# Sheet1.net
KiCad netlist of a schematic drawn in Altium Designer
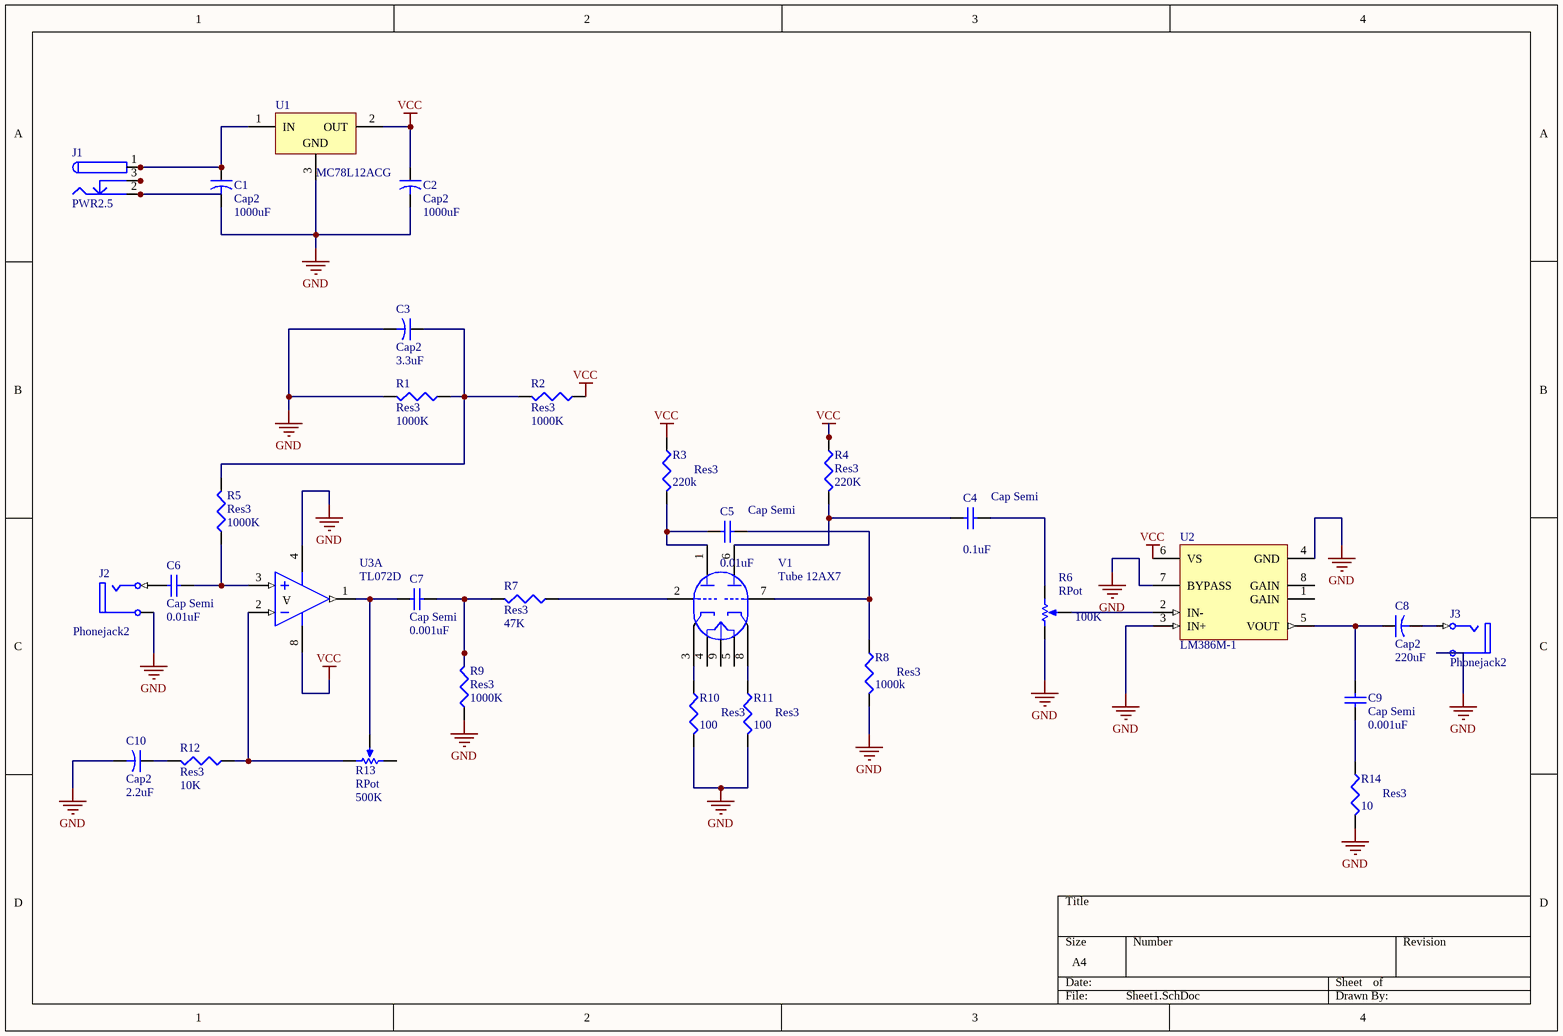
[diagram p0: Sheet1.SchDoc]

(export (version "E")
  (design (tool "Eeschema 10.0.6"))
  (components
    (comp (ref "C1")
      (value "Cap2")
      (footprint "CAPR5-4X5")
      (description "Capacitor")
      (fields (field (name "ALTIUM_VALUE") "1000uF") (field (name "PUBLISHER") "Altium Limited"))
      (libsource (lib "Miscellaneous Devices") (part "Cap2"))
    )
    (comp (ref "C2")
      (value "Cap2")
      (footprint "CAPR5-4X5")
      (description "Capacitor")
      (fields (field (name "ALTIUM_VALUE") "1000uF") (field (name "PUBLISHER") "Altium Limited"))
      (libsource (lib "Miscellaneous Devices") (part "Cap2"))
    )
    (comp (ref "C3")
      (value "Cap2")
      (footprint "CAPR5-4X5")
      (description "Capacitor")
      (fields (field (name "ALTIUM_VALUE") "3.3uF") (field (name "PUBLISHER") "Altium Limited"))
      (libsource (lib "Miscellaneous Devices") (part "Cap2"))
    )
    (comp (ref "C4")
      (value "Cap Semi")
      (footprint "C1206")
      (description "Capacitor (Semiconductor SIM Model)")
      (fields (field (name "ALTIUM_VALUE") "0.1uF") (field (name "PUBLISHER") "Altium Limited"))
      (libsource (lib "Miscellaneous Devices") (part "Cap Semi"))
    )
    (comp (ref "C5")
      (value "Cap Semi")
      (footprint "C1206")
      (description "Capacitor (Semiconductor SIM Model)")
      (fields (field (name "ALTIUM_VALUE") "0.01uF") (field (name "PUBLISHER") "Altium Limited"))
      (libsource (lib "Miscellaneous Devices") (part "Cap Semi"))
    )
    (comp (ref "C6")
      (value "Cap Semi")
      (footprint "1608[0603]")
      (description "Capacitor (Semiconductor SIM Model)")
      (fields (field (name "ALTIUM_VALUE") "0.01uF") (field (name "PUBLISHER") "Altium Limited"))
      (libsource (lib "Miscellaneous Devices") (part "Cap Semi"))
    )
    (comp (ref "C7")
      (value "Cap Semi")
      (footprint "C1206")
      (description "Capacitor (Semiconductor SIM Model)")
      (fields (field (name "ALTIUM_VALUE") "0.001uF") (field (name "PUBLISHER") "Altium Limited"))
      (libsource (lib "Miscellaneous Devices") (part "Cap Semi"))
    )
    (comp (ref "C8")
      (value "Cap2")
      (footprint "CAPR5-4X5")
      (description "Capacitor")
      (fields (field (name "ALTIUM_VALUE") "220uF") (field (name "PUBLISHER") "Altium Limited"))
      (libsource (lib "Miscellaneous Devices") (part "Cap2"))
    )
    (comp (ref "C9")
      (value "Cap Semi")
      (footprint "C1206")
      (description "Capacitor (Semiconductor SIM Model)")
      (fields (field (name "ALTIUM_VALUE") "0.001uF") (field (name "PUBLISHER") "Altium Limited"))
      (libsource (lib "Miscellaneous Devices") (part "Cap Semi"))
    )
    (comp (ref "C10")
      (value "Cap2")
      (footprint "CAPR5-4X5")
      (description "Capacitor")
      (fields (field (name "ALTIUM_VALUE") "2.2uF") (field (name "PUBLISHER") "Altium Limited"))
      (libsource (lib "Miscellaneous Devices") (part "Cap2"))
    )
    (comp (ref "J1")
      (value "PWR2.5")
      (footprint "KLD-0202")
      (description "Low Voltage Power Supply Connector")
      (fields (field (name "PUBLISHER") "Altium Limited"))
      (libsource (lib "Miscellaneous Connectors") (part "PWR2.5"))
    )
    (comp (ref "J2")
      (value "Phonejack2")
      (footprint "JACK/6-V2")
      (description "Jack Socket, 1/4\" [6.5mm], Thru-Hole, Vertical, 2-Conductor Open Circuit")
      (fields (field (name "PUBLISHER") "Altium Limited"))
      (libsource (lib "Miscellaneous Connectors") (part "Phonejack2"))
    )
    (comp (ref "J3")
      (value "Phonejack2")
      (footprint "JACK/6-V2")
      (description "Jack Socket, 1/4\" [6.5mm], Thru-Hole, Vertical, 2-Conductor Open Circuit")
      (fields (field (name "PUBLISHER") "Altium Limited"))
      (libsource (lib "Miscellaneous Connectors") (part "Phonejack2"))
    )
    (comp (ref "R1")
      (value "Res3")
      (footprint "J1-0603")
      (description "Resistor")
      (fields (field (name "ALTIUM_VALUE") "1000K") (field (name "PUBLISHER") "Altium Limited"))
      (libsource (lib "Miscellaneous Devices") (part "Res3"))
    )
    (comp (ref "R2")
      (value "Res3")
      (footprint "J1-0603")
      (description "Resistor")
      (fields (field (name "ALTIUM_VALUE") "1000K") (field (name "PUBLISHER") "Altium Limited"))
      (libsource (lib "Miscellaneous Devices") (part "Res3"))
    )
    (comp (ref "R3")
      (value "Res3")
      (footprint "J1-0603")
      (description "Resistor")
      (fields (field (name "ALTIUM_VALUE") "220k") (field (name "PUBLISHER") "Altium Limited"))
      (libsource (lib "Miscellaneous Devices") (part "Res3"))
    )
    (comp (ref "R4")
      (value "Res3")
      (footprint "J1-0603")
      (description "Resistor")
      (fields (field (name "ALTIUM_VALUE") "220K") (field (name "PUBLISHER") "Altium Limited"))
      (libsource (lib "Miscellaneous Devices") (part "Res3"))
    )
    (comp (ref "R5")
      (value "Res3")
      (footprint "J1-0603")
      (description "Resistor")
      (fields (field (name "ALTIUM_VALUE") "1000K") (field (name "PUBLISHER") "Altium Limited"))
      (libsource (lib "Miscellaneous Devices") (part "Res3"))
    )
    (comp (ref "R6")
      (value "RPot")
      (footprint "VR5")
      (description "Potentiometer")
      (fields (field (name "ALTIUM_VALUE") "100K") (field (name "PUBLISHER") "Altium Limited"))
      (libsource (lib "Miscellaneous Devices") (part "RPot"))
    )
    (comp (ref "R7")
      (value "Res3")
      (footprint "J1-0603")
      (description "Resistor")
      (fields (field (name "ALTIUM_VALUE") "47K") (field (name "PUBLISHER") "Altium Limited"))
      (libsource (lib "Miscellaneous Devices") (part "Res3"))
    )
    (comp (ref "R8")
      (value "Res3")
      (footprint "J1-0603")
      (description "Resistor")
      (fields (field (name "ALTIUM_VALUE") "1000k") (field (name "PUBLISHER") "Altium Limited"))
      (libsource (lib "Miscellaneous Devices") (part "Res3"))
    )
    (comp (ref "R9")
      (value "Res3")
      (footprint "J1-0603")
      (description "Resistor")
      (fields (field (name "ALTIUM_VALUE") "1000K") (field (name "PUBLISHER") "Altium Limited"))
      (libsource (lib "Miscellaneous Devices") (part "Res3"))
    )
    (comp (ref "R10")
      (value "Res3")
      (footprint "J1-0603")
      (description "Resistor")
      (fields (field (name "ALTIUM_VALUE") "100") (field (name "PUBLISHER") "Altium Limited"))
      (libsource (lib "Miscellaneous Devices") (part "Res3"))
    )
    (comp (ref "R11")
      (value "Res3")
      (footprint "J1-0603")
      (description "Resistor")
      (fields (field (name "ALTIUM_VALUE") "100") (field (name "PUBLISHER") "Altium Limited"))
      (libsource (lib "Miscellaneous Devices") (part "Res3"))
    )
    (comp (ref "R12")
      (value "Res3")
      (footprint "J1-0603")
      (description "Resistor")
      (fields (field (name "ALTIUM_VALUE") "10K") (field (name "PUBLISHER") "Altium Limited"))
      (libsource (lib "Miscellaneous Devices") (part "Res3"))
    )
    (comp (ref "R13")
      (value "RPot")
      (footprint "VR5")
      (description "Potentiometer")
      (fields (field (name "ALTIUM_VALUE") "500K") (field (name "PUBLISHER") "Altium Limited"))
      (libsource (lib "Miscellaneous Devices") (part "RPot"))
    )
    (comp (ref "R14")
      (value "Res3")
      (footprint "J1-0603")
      (description "Resistor")
      (fields (field (name "ALTIUM_VALUE") "10") (field (name "PUBLISHER") "Altium Limited"))
      (libsource (lib "Miscellaneous Devices") (part "Res3"))
    )
    (comp (ref "U1")
      (value "MC78L12ACG")
      (footprint "79-05")
      (description "3-Terminal Low-Current Positive Fixed Voltage Regulator")
      (fields (field (name "PUBLISHER") "Altium Limited"))
      (libsource (lib "Motorola Power Mgt Voltage Regulator") (part "MC78L12ACG"))
    )
    (comp (ref "U2")
      (value "LM386M-1")
      (footprint "M08A_N")
      (description "Low Voltage Audio Power Amplifier, 8-pin Narrow SOIC")
      (fields
        (field (name "MANUFACTURER") "National Semiconductor")
        (field (name "PUBLISHER") "Altium Limited")
      )
      (libsource (lib "NSC Audio") (part "LM386M-1"))
    )
    (comp (ref "U3")
      (value "TL072D")
      (footprint "D008_M")
      (description "Low-Noise JFET-Input Operational Amplifier")
      (fields (field (name "PUBLISHER") "Altium Limited"))
      (libsource (lib "TI Operational Amplifier") (part "TL072D"))
    )
    (comp (ref "V1")
      (value "Tube 12AX7")
      (footprint "VTUBE-9")
      (description "High Mu Dual Triode")
      (fields (field (name "PUBLISHER") "Altium Limited"))
      (libsource (lib "Miscellaneous Devices") (part "Tube 12AX7"))
    )
  )
  (nets
    (net (code "1") (name "GND") (class "Default")
      (node (ref "C1") (pin "2") (pinfunction "2_2") (pintype "passive"))
      (node (ref "C10") (pin "2") (pinfunction "2_2") (pintype "passive"))
      (node (ref "C2") (pin "2") (pinfunction "2_2") (pintype "passive"))
      (node (ref "C3") (pin "2") (pinfunction "2_2") (pintype "passive"))
      (node (ref "J2") (pin "5") (pinfunction "S_5") (pintype "power_in"))
      (node (ref "J3") (pin "5") (pinfunction "S_5") (pintype "power_in"))
      (node (ref "R1") (pin "2") (pinfunction "2_2") (pintype "passive"))
      (node (ref "R10") (pin "2") (pinfunction "2_2") (pintype "passive"))
      (node (ref "R11") (pin "2") (pinfunction "2_2") (pintype "passive"))
      (node (ref "R14") (pin "2") (pinfunction "2_2") (pintype "passive"))
      (node (ref "R6") (pin "1") (pinfunction "TOP_1") (pintype "passive"))
      (node (ref "R8") (pin "2") (pinfunction "2_2") (pintype "passive"))
      (node (ref "R9") (pin "1") (pinfunction "1_1") (pintype "passive"))
      (node (ref "U1") (pin "3") (pinfunction "GND_3") (pintype "power_in"))
      (node (ref "U2") (pin "3") (pinfunction "IN+_3") (pintype "input"))
      (node (ref "U2") (pin "4") (pinfunction "GND_4") (pintype "power_in"))
      (node (ref "U2") (pin "7") (pinfunction "BYPASS_7") (pintype "passive"))
      (node (ref "U3") (pin "4") (pinfunction "V-_4") (pintype "power_in"))
    )
    (net (code "2") (name "Net-(C3-Pad1)") (class "Default")
      (node (ref "C3") (pin "1") (pinfunction "1_1") (pintype "passive"))
      (node (ref "R1") (pin "1") (pinfunction "1_1") (pintype "passive"))
      (node (ref "R2") (pin "2") (pinfunction "2_2") (pintype "passive"))
      (node (ref "R5") (pin "2") (pinfunction "2_2") (pintype "passive"))
    )
    (net (code "3") (name "Net-(C7-Pad2)") (class "Default")
      (node (ref "C7") (pin "2") (pinfunction "2_2") (pintype "passive"))
      (node (ref "R7") (pin "2") (pinfunction "2_2") (pintype "passive"))
      (node (ref "R9") (pin "2") (pinfunction "2_2") (pintype "passive"))
    )
    (net (code "4") (name "Net-(C9-Pad1)") (class "Default")
      (node (ref "C9") (pin "1") (pinfunction "1_1") (pintype "passive"))
      (node (ref "R14") (pin "1") (pinfunction "1_1") (pintype "passive"))
    )
    (net (code "5") (name "Net-(C10-Pad1)") (class "Default")
      (node (ref "C10") (pin "1") (pinfunction "1_1") (pintype "passive"))
      (node (ref "R12") (pin "2") (pinfunction "2_2") (pintype "passive"))
    )
    (net (code "6") (name "Net-(J1-Pad2)") (class "Default")
      (node (ref "J1") (pin "2") (pinfunction "2_2") (pintype "power_in"))
      (node (ref "J1") (pin "2A") (pinfunction "2A_2A") (pintype "power_in"))
      (node (ref "J1") (pin "2B") (pinfunction "2B_2B") (pintype "power_in"))
    )
    (net (code "7") (name "Net-(J1-Pad3)") (class "Default")
      (node (ref "J1") (pin "3") (pinfunction "3_3") (pintype "power_in"))
      (node (ref "J1") (pin "3A") (pinfunction "3A_3A") (pintype "power_in"))
      (node (ref "J1") (pin "3B") (pinfunction "3B_3B") (pintype "power_in"))
    )
    (net (code "8") (name "Net-(J2-T)") (class "Default")
      (node (ref "C6") (pin "1") (pinfunction "1_1") (pintype "passive"))
      (node (ref "J2") (pin "1") (pinfunction "T_1") (pintype "input"))
    )
    (net (code "9") (name "Net-(J3-T)") (class "Default")
      (node (ref "C8") (pin "2") (pinfunction "2_2") (pintype "passive"))
      (node (ref "J3") (pin "1") (pinfunction "T_1") (pintype "input"))
    )
    (net (code "10") (name "Net-(R6-BOT)") (class "Default")
      (node (ref "C4") (pin "2") (pinfunction "2_2") (pintype "passive"))
      (node (ref "R6") (pin "2") (pinfunction "BOT_2") (pintype "passive"))
    )
    (net (code "11") (name "Net-(R6-TAP)") (class "Default")
      (node (ref "R6") (pin "3") (pinfunction "TAP_3") (pintype "passive"))
      (node (ref "U2") (pin "2") (pinfunction "IN-_2") (pintype "input"))
    )
    (net (code "12") (name "Net-(R13-BOT)") (class "Default")
      (node (ref "R12") (pin "1") (pinfunction "1_1") (pintype "passive"))
      (node (ref "R13") (pin "2") (pinfunction "BOT_2") (pintype "passive"))
      (node (ref "U3") (pin "2") (pinfunction "IN-_2") (pintype "input"))
    )
    (net (code "13") (name "Net-(R13-TAP)") (class "Default")
      (node (ref "C7") (pin "1") (pinfunction "1_1") (pintype "passive"))
      (node (ref "R13") (pin "3") (pinfunction "TAP_3") (pintype "passive"))
      (node (ref "U3") (pin "1") (pinfunction "OUT_1") (pintype "output"))
    )
    (net (code "14") (name "Net-(U1-IN)") (class "Default")
      (node (ref "C1") (pin "1") (pinfunction "1_1") (pintype "passive"))
      (node (ref "J1") (pin "1") (pinfunction "1_1") (pintype "power_in"))
      (node (ref "J1") (pin "1A") (pinfunction "1A_1A") (pintype "power_in"))
      (node (ref "J1") (pin "1B") (pinfunction "1B_1B") (pintype "power_in"))
      (node (ref "U1") (pin "1") (pinfunction "IN_1") (pintype "power_in"))
    )
    (net (code "15") (name "Net-(U2-VOUT)") (class "Default")
      (node (ref "C8") (pin "1") (pinfunction "1_1") (pintype "passive"))
      (node (ref "C9") (pin "2") (pinfunction "2_2") (pintype "passive"))
      (node (ref "U2") (pin "5") (pinfunction "VOUT_5") (pintype "output"))
    )
    (net (code "16") (name "Net-(U3A-IN+)") (class "Default")
      (node (ref "C6") (pin "2") (pinfunction "2_2") (pintype "passive"))
      (node (ref "R5") (pin "1") (pinfunction "1_1") (pintype "passive"))
      (node (ref "U3") (pin "3") (pinfunction "IN+_3") (pintype "input"))
    )
    (net (code "17") (name "Net-(V1-GT1)") (class "Default")
      (node (ref "R7") (pin "1") (pinfunction "1_1") (pintype "passive"))
      (node (ref "V1") (pin "2") (pinfunction "GT1_2") (pintype "passive"))
    )
    (net (code "18") (name "Net-(V1-GT2)") (class "Default")
      (node (ref "C5") (pin "2") (pinfunction "2_2") (pintype "passive"))
      (node (ref "R8") (pin "1") (pinfunction "1_1") (pintype "passive"))
      (node (ref "V1") (pin "7") (pinfunction "GT2_7") (pintype "passive"))
    )
    (net (code "19") (name "Net-(V1-KT1)") (class "Default")
      (node (ref "R10") (pin "1") (pinfunction "1_1") (pintype "passive"))
      (node (ref "V1") (pin "3") (pinfunction "KT1_3") (pintype "passive"))
    )
    (net (code "20") (name "Net-(V1-KT2)") (class "Default")
      (node (ref "R11") (pin "1") (pinfunction "1_1") (pintype "passive"))
      (node (ref "V1") (pin "8") (pinfunction "KT2_8") (pintype "passive"))
    )
    (net (code "21") (name "Net-(V1-PT1)") (class "Default")
      (node (ref "C5") (pin "1") (pinfunction "1_1") (pintype "passive"))
      (node (ref "R3") (pin "2") (pinfunction "2_2") (pintype "passive"))
      (node (ref "V1") (pin "1") (pinfunction "PT1_1") (pintype "passive"))
    )
    (net (code "22") (name "Net-(V1-PT2)") (class "Default")
      (node (ref "C4") (pin "1") (pinfunction "1_1") (pintype "passive"))
      (node (ref "R4") (pin "2") (pinfunction "2_2") (pintype "passive"))
      (node (ref "V1") (pin "6") (pinfunction "PT2_6") (pintype "passive"))
    )
    (net (code "23") (name "VCC") (class "Default")
      (node (ref "C2") (pin "1") (pinfunction "1_1") (pintype "passive"))
      (node (ref "R2") (pin "1") (pinfunction "1_1") (pintype "passive"))
      (node (ref "R3") (pin "1") (pinfunction "1_1") (pintype "passive"))
      (node (ref "R4") (pin "1") (pinfunction "1_1") (pintype "passive"))
      (node (ref "U1") (pin "2") (pinfunction "OUT_2") (pintype "power_in"))
      (node (ref "U2") (pin "6") (pinfunction "VS_6") (pintype "power_in"))
      (node (ref "U3") (pin "8") (pinfunction "V+_8") (pintype "power_in"))
    )
    (net (code "24") (name "unconnected-(R13-TOP-Pad1)") (class "Default")
      (node (ref "R13") (pin "1") (pinfunction "TOP_1") (pintype "passive"))
    )
    (net (code "25") (name "unconnected-(U2-GAIN-Pad1)") (class "Default")
      (node (ref "U2") (pin "1") (pinfunction "GAIN_1") (pintype "passive"))
    )
    (net (code "26") (name "unconnected-(U2-GAIN-Pad8)") (class "Default")
      (node (ref "U2") (pin "8") (pinfunction "GAIN_8") (pintype "passive"))
    )
    (net (code "27") (name "unconnected-(V1-H-Pad4)") (class "Default")
      (node (ref "V1") (pin "4") (pinfunction "H_4") (pintype "passive"))
    )
    (net (code "28") (name "unconnected-(V1-H-Pad5)") (class "Default")
      (node (ref "V1") (pin "5") (pinfunction "H_5") (pintype "passive"))
    )
    (net (code "29") (name "unconnected-(V1-HM-Pad9)") (class "Default")
      (node (ref "V1") (pin "9") (pinfunction "HM_9") (pintype "passive"))
    )
  )
)
